# NRF24L01P.net
KiCad netlist of a schematic drawn in Altium Designer
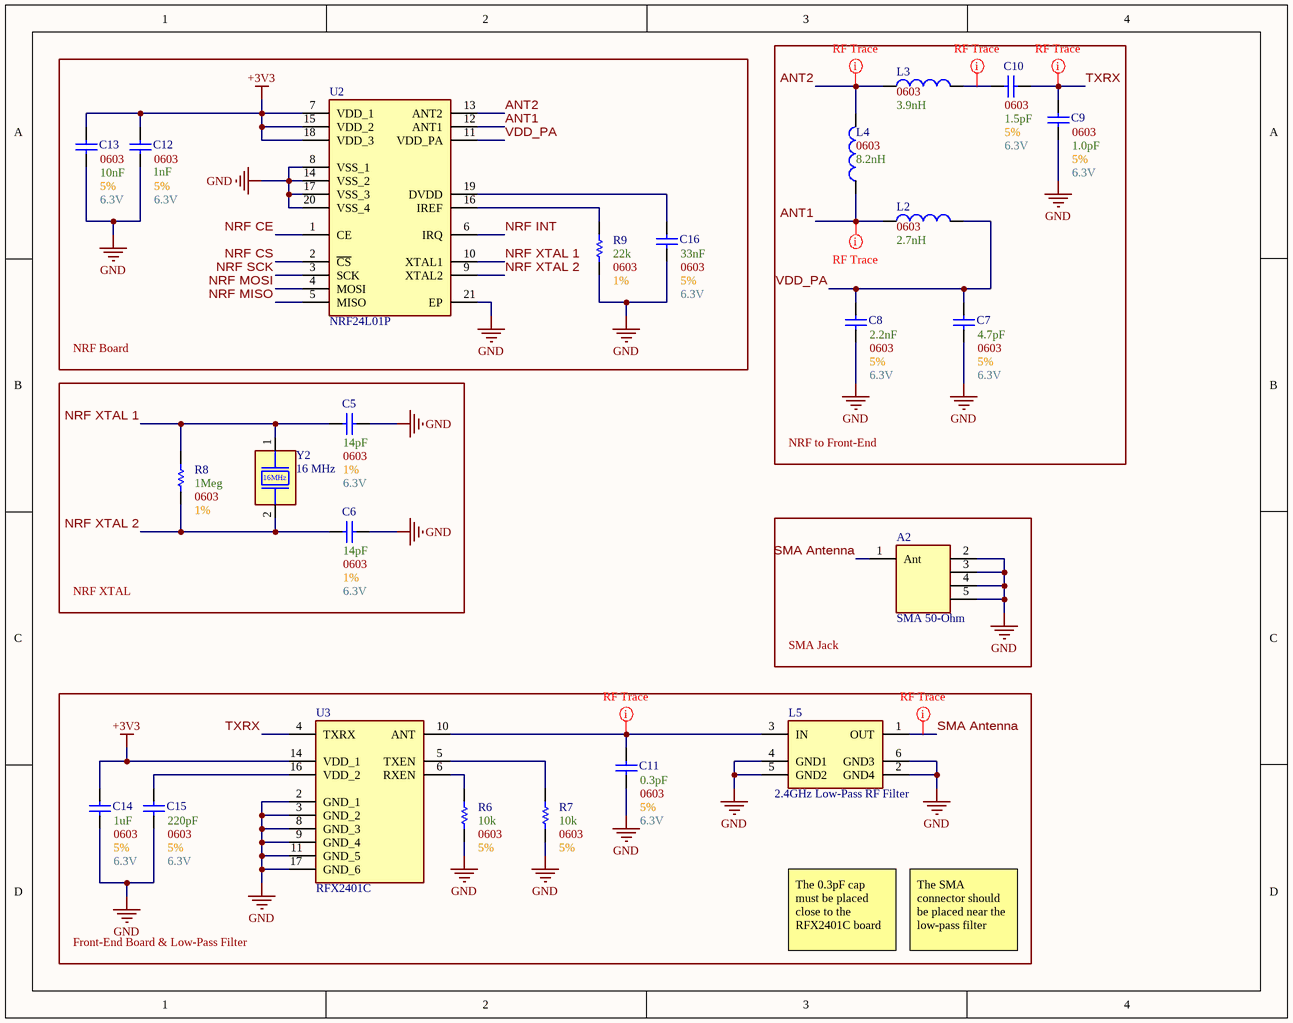
[diagram p0: NRF24L01P.SchDoc]

(export (version "E")
  (design (tool "Eeschema 10.0.6"))
  (components
    (comp (ref "A2")
      (value "SMA 50-Ohm")
      (footprint "[SMA] 90deg Jack")
      (description "SMA-J-P-H-RA-TH1")
      (libsource (lib "RADM Connectors") (part "[SMA] 90deg Jack"))
    )
    (comp (ref "C5")
      (value "SMD Nonpolarized")
      (footprint "[Cap] SMD 0603")
      (fields
        (field (name "TOLERANCE") "1%")
        (field (name "SIZE PACKAGE") "0603")
        (field (name "CAPACITANCE") "14pF")
        (field (name "VOLTAGE") "6.3V")
      )
      (libsource (lib "RADM Components") (part "[Cap] SMD Nonpolarized"))
    )
    (comp (ref "C6")
      (value "SMD Nonpolarized")
      (footprint "[Cap] SMD 0603")
      (fields
        (field (name "TOLERANCE") "1%")
        (field (name "SIZE PACKAGE") "0603")
        (field (name "CAPACITANCE") "14pF")
        (field (name "VOLTAGE") "6.3V")
      )
      (libsource (lib "RADM Components") (part "[Cap] SMD Nonpolarized"))
    )
    (comp (ref "C7")
      (value "SMD Nonpolarized")
      (footprint "[Cap] SMD 0603")
      (fields
        (field (name "TOLERANCE") "5%")
        (field (name "SIZE PACKAGE") "0603")
        (field (name "CAPACITANCE") "4.7pF")
        (field (name "VOLTAGE") "6.3V")
      )
      (libsource (lib "RADM Components") (part "[Cap] SMD Nonpolarized"))
    )
    (comp (ref "C8")
      (value "SMD Nonpolarized")
      (footprint "[Cap] SMD 0603")
      (fields
        (field (name "TOLERANCE") "5%")
        (field (name "SIZE PACKAGE") "0603")
        (field (name "CAPACITANCE") "2.2nF")
        (field (name "VOLTAGE") "6.3V")
      )
      (libsource (lib "RADM Components") (part "[Cap] SMD Nonpolarized"))
    )
    (comp (ref "C9")
      (value "SMD Nonpolarized")
      (footprint "[Cap] SMD 0603")
      (fields
        (field (name "TOLERANCE") "5%")
        (field (name "SIZE PACKAGE") "0603")
        (field (name "CAPACITANCE") "1.0pF")
        (field (name "VOLTAGE") "6.3V")
      )
      (libsource (lib "RADM Components") (part "[Cap] SMD Nonpolarized"))
    )
    (comp (ref "C10")
      (value "SMD Nonpolarized")
      (footprint "[Cap] SMD 0603")
      (fields
        (field (name "TOLERANCE") "5%")
        (field (name "SIZE PACKAGE") "0603")
        (field (name "CAPACITANCE") "1.5pF")
        (field (name "VOLTAGE") "6.3V")
      )
      (libsource (lib "RADM Components") (part "[Cap] SMD Nonpolarized"))
    )
    (comp (ref "C11")
      (value "SMD Nonpolarized")
      (footprint "[Cap] SMD 0603")
      (fields
        (field (name "TOLERANCE") "5%")
        (field (name "SIZE PACKAGE") "0603")
        (field (name "CAPACITANCE") "0.3pF")
        (field (name "VOLTAGE") "6.3V")
      )
      (libsource (lib "RADM Components") (part "[Cap] SMD Nonpolarized"))
    )
    (comp (ref "C12")
      (value "SMD Nonpolarized")
      (footprint "[Cap] SMD 0603")
      (fields
        (field (name "TOLERANCE") "5%")
        (field (name "SIZE PACKAGE") "0603")
        (field (name "CAPACITANCE") "1nF")
        (field (name "VOLTAGE") "6.3V")
      )
      (libsource (lib "RADM Components") (part "[Cap] SMD Nonpolarized"))
    )
    (comp (ref "C13")
      (value "SMD Nonpolarized")
      (footprint "[Cap] SMD 0603")
      (fields
        (field (name "TOLERANCE") "5%")
        (field (name "SIZE PACKAGE") "0603")
        (field (name "CAPACITANCE") "10nF")
        (field (name "VOLTAGE") "6.3V")
      )
      (libsource (lib "RADM Components") (part "[Cap] SMD Nonpolarized"))
    )
    (comp (ref "C14")
      (value "SMD Nonpolarized")
      (footprint "[Cap] SMD 0603")
      (fields
        (field (name "TOLERANCE") "5%")
        (field (name "SIZE PACKAGE") "0603")
        (field (name "CAPACITANCE") "1uF")
        (field (name "VOLTAGE") "6.3V")
      )
      (libsource (lib "RADM Components") (part "[Cap] SMD Nonpolarized"))
    )
    (comp (ref "C15")
      (value "SMD Nonpolarized")
      (footprint "[Cap] SMD 0603")
      (fields
        (field (name "TOLERANCE") "5%")
        (field (name "SIZE PACKAGE") "0603")
        (field (name "CAPACITANCE") "220pF")
        (field (name "VOLTAGE") "6.3V")
      )
      (libsource (lib "RADM Components") (part "[Cap] SMD Nonpolarized"))
    )
    (comp (ref "C16")
      (value "SMD Nonpolarized")
      (footprint "[Cap] SMD 0603")
      (fields
        (field (name "TOLERANCE") "5%")
        (field (name "SIZE PACKAGE") "0603")
        (field (name "CAPACITANCE") "33nF")
        (field (name "VOLTAGE") "6.3V")
      )
      (libsource (lib "RADM Components") (part "[Cap] SMD Nonpolarized"))
    )
    (comp (ref "L2")
      (value "SMD Inductor")
      (footprint "[Inductor] SMD 0603")
      (fields (field (name "SIZE PACKAGE") "0603") (field (name "INDUCTANCE") "2.7nH"))
      (libsource (lib "RADM Components") (part "[Inductor] SMD Inductor"))
    )
    (comp (ref "L3")
      (value "SMD Inductor")
      (footprint "[Inductor] SMD 0603")
      (fields (field (name "SIZE PACKAGE") "0603") (field (name "INDUCTANCE") "3.9nH"))
      (libsource (lib "RADM Components") (part "[Inductor] SMD Inductor"))
    )
    (comp (ref "L4")
      (value "SMD Inductor")
      (footprint "[Inductor] SMD 0603")
      (fields (field (name "SIZE PACKAGE") "0603") (field (name "INDUCTANCE") "8.2nH"))
      (libsource (lib "RADM Components") (part "[Inductor] SMD Inductor"))
    )
    (comp (ref "L5")
      (value "2.4GHz Low-Pass RF Filter")
      (footprint "[Inductor] 2.4GHz Low-Pass RF Filter")
      (description "MLPF-NRG-01D3")
      (libsource (lib "RADM Components") (part "[Inductor] 2.4GHz Low-Pass RF Filter"))
    )
    (comp (ref "R6")
      (value "[Res] SMD Resistor")
      (footprint "[Res] SMD 0603")
      (description "Generic")
      (fields
        (field (name "TOLERANCE") "5%")
        (field (name "RESISTANCE") "10k")
        (field (name "SIZE PACKAGE") "0603")
      )
      (libsource (lib "RADM Components") (part "[Res] SMD Resistor"))
    )
    (comp (ref "R7")
      (value "[Res] SMD Resistor")
      (footprint "[Res] SMD 0603")
      (description "Generic")
      (fields
        (field (name "TOLERANCE") "5%")
        (field (name "RESISTANCE") "10k")
        (field (name "SIZE PACKAGE") "0603")
      )
      (libsource (lib "RADM Components") (part "[Res] SMD Resistor"))
    )
    (comp (ref "R8")
      (value "[Res] SMD Resistor")
      (footprint "[Res] SMD 0603")
      (description "Generic")
      (fields
        (field (name "TOLERANCE") "1%")
        (field (name "RESISTANCE") "1Meg")
        (field (name "SIZE PACKAGE") "0603")
      )
      (libsource (lib "RADM Components") (part "[Res] SMD Resistor"))
    )
    (comp (ref "R9")
      (value "[Res] SMD Resistor")
      (footprint "[Res] SMD 0603")
      (description "Generic")
      (fields
        (field (name "TOLERANCE") "1%")
        (field (name "RESISTANCE") "22k")
        (field (name "SIZE PACKAGE") "0603")
      )
      (libsource (lib "RADM Components") (part "[Res] SMD Resistor"))
    )
    (comp (ref "U2")
      (value "NRF24L01P")
      (footprint "[IC] NRF Transceiver")
      (description "NRF24L01P-R")
      (libsource (lib "RADM Components") (part "[IC] NRF Transceiver"))
    )
    (comp (ref "U3")
      (value "RFX2401C")
      (footprint "[IC] RF Front-End")
      (libsource (lib "RADM Components") (part "[IC] RF Front-End"))
    )
    (comp (ref "Y2")
      (value "16 MHz")
      (footprint "[XTAL] SMD 16MHz (2)")
      (description "ABM11-16.000MHZ-12-N1G-T")
      (libsource (lib "RADM Components") (part "[XTAL] SMD 16MHz (2)"))
    )
  )
  (nets
    (net (code "1") (name "+3V3") (class "Default")
      (node (ref "C12") (pin "2") (pinfunction "2_2") (pintype "passive"))
      (node (ref "C13") (pin "2") (pinfunction "2_2") (pintype "passive"))
      (node (ref "C14") (pin "2") (pinfunction "2_2") (pintype "passive"))
      (node (ref "U2") (pin "15") (pinfunction "VDD_2_15") (pintype "passive"))
      (node (ref "U2") (pin "18") (pinfunction "VDD_3_18") (pintype "passive"))
      (node (ref "U2") (pin "7") (pinfunction "VDD_1_7") (pintype "passive"))
      (node (ref "U3") (pin "14") (pinfunction "VDD_1_14") (pintype "passive"))
    )
    (net (code "2") (name "/ANT1") (class "Default")
      (node (ref "L2") (pin "1") (pinfunction "1_1") (pintype "passive"))
      (node (ref "L4") (pin "1") (pinfunction "1_1") (pintype "passive"))
      (node (ref "U2") (pin "12") (pinfunction "ANT1_12") (pintype "passive"))
    )
    (net (code "3") (name "/ANT2") (class "Default")
      (node (ref "L3") (pin "1") (pinfunction "1_1") (pintype "passive"))
      (node (ref "L4") (pin "2") (pinfunction "2_2") (pintype "passive"))
      (node (ref "U2") (pin "13") (pinfunction "ANT2_13") (pintype "passive"))
    )
    (net (code "4") (name "/NRF CE") (class "Default")
      (node (ref "U2") (pin "1") (pinfunction "CE_1") (pintype "passive"))
    )
    (net (code "5") (name "/NRF CS") (class "Default")
      (node (ref "U2") (pin "2") (pinfunction "CS_2") (pintype "passive"))
    )
    (net (code "6") (name "/NRF INT") (class "Default")
      (node (ref "U2") (pin "6") (pinfunction "IRQ_6") (pintype "passive"))
    )
    (net (code "7") (name "/NRF MISO") (class "Default")
      (node (ref "U2") (pin "5") (pinfunction "MISO_5") (pintype "passive"))
    )
    (net (code "8") (name "/NRF MOSI") (class "Default")
      (node (ref "U2") (pin "4") (pinfunction "MOSI_4") (pintype "passive"))
    )
    (net (code "9") (name "/NRF SCK") (class "Default")
      (node (ref "U2") (pin "3") (pinfunction "SCK_3") (pintype "passive"))
    )
    (net (code "10") (name "/NRF XTAL 1") (class "Default")
      (node (ref "C5") (pin "1") (pinfunction "1_1") (pintype "passive"))
      (node (ref "R8") (pin "2") (pinfunction "2_2") (pintype "passive"))
      (node (ref "U2") (pin "10") (pinfunction "XTAL1_10") (pintype "passive"))
      (node (ref "Y2") (pin "1") (pinfunction "XTAL1_1") (pintype "passive"))
    )
    (net (code "11") (name "/NRF XTAL 2") (class "Default")
      (node (ref "C6") (pin "1") (pinfunction "1_1") (pintype "passive"))
      (node (ref "R8") (pin "1") (pinfunction "1_1") (pintype "passive"))
      (node (ref "U2") (pin "9") (pinfunction "XTAL2_9") (pintype "passive"))
      (node (ref "Y2") (pin "2") (pinfunction "XTAL2_2") (pintype "passive"))
    )
    (net (code "12") (name "/SMA Antenna") (class "Default")
      (node (ref "A2") (pin "1") (pinfunction "Ant_1") (pintype "passive"))
      (node (ref "L5") (pin "1") (pinfunction "OUT_1") (pintype "passive"))
    )
    (net (code "13") (name "/TXRX") (class "Default")
      (node (ref "C10") (pin "1") (pinfunction "1_1") (pintype "passive"))
      (node (ref "C9") (pin "1") (pinfunction "1_1") (pintype "passive"))
      (node (ref "U3") (pin "4") (pinfunction "TXRX_4") (pintype "passive"))
    )
    (net (code "14") (name "/VDD_PA") (class "Default")
      (node (ref "C7") (pin "2") (pinfunction "2_2") (pintype "passive"))
      (node (ref "C8") (pin "2") (pinfunction "2_2") (pintype "passive"))
      (node (ref "L2") (pin "2") (pinfunction "2_2") (pintype "passive"))
      (node (ref "U2") (pin "11") (pinfunction "VDD_PA_11") (pintype "passive"))
    )
    (net (code "15") (name "GND") (class "Default")
      (node (ref "A2") (pin "2") (pinfunction "2_2") (pintype "passive"))
      (node (ref "A2") (pin "3") (pinfunction "3_3") (pintype "passive"))
      (node (ref "A2") (pin "4") (pinfunction "4_4") (pintype "passive"))
      (node (ref "A2") (pin "5") (pinfunction "5_5") (pintype "passive"))
      (node (ref "C11") (pin "1") (pinfunction "1_1") (pintype "passive"))
      (node (ref "C12") (pin "1") (pinfunction "1_1") (pintype "passive"))
      (node (ref "C13") (pin "1") (pinfunction "1_1") (pintype "passive"))
      (node (ref "C14") (pin "1") (pinfunction "1_1") (pintype "passive"))
      (node (ref "C15") (pin "1") (pinfunction "1_1") (pintype "passive"))
      (node (ref "C16") (pin "1") (pinfunction "1_1") (pintype "passive"))
      (node (ref "C5") (pin "2") (pinfunction "2_2") (pintype "passive"))
      (node (ref "C6") (pin "2") (pinfunction "2_2") (pintype "passive"))
      (node (ref "C7") (pin "1") (pinfunction "1_1") (pintype "passive"))
      (node (ref "C8") (pin "1") (pinfunction "1_1") (pintype "passive"))
      (node (ref "C9") (pin "2") (pinfunction "2_2") (pintype "passive"))
      (node (ref "L5") (pin "2") (pinfunction "GND4_2") (pintype "passive"))
      (node (ref "L5") (pin "4") (pinfunction "GND1_4") (pintype "passive"))
      (node (ref "L5") (pin "5") (pinfunction "GND2_5") (pintype "passive"))
      (node (ref "L5") (pin "6") (pinfunction "GND3_6") (pintype "passive"))
      (node (ref "R6") (pin "1") (pinfunction "1_1") (pintype "passive"))
      (node (ref "R7") (pin "1") (pinfunction "1_1") (pintype "passive"))
      (node (ref "R9") (pin "1") (pinfunction "1_1") (pintype "passive"))
      (node (ref "U2") (pin "14") (pinfunction "VSS_2_14") (pintype "passive"))
      (node (ref "U2") (pin "17") (pinfunction "VSS_3_17") (pintype "passive"))
      (node (ref "U2") (pin "20") (pinfunction "VSS_4_20") (pintype "passive"))
      (node (ref "U2") (pin "21") (pinfunction "EP_21") (pintype "passive"))
      (node (ref "U2") (pin "8") (pinfunction "VSS_1_8") (pintype "passive"))
      (node (ref "U3") (pin "11") (pinfunction "GND_5_11") (pintype "passive"))
      (node (ref "U3") (pin "17") (pinfunction "GND_6_17") (pintype "passive"))
      (node (ref "U3") (pin "2") (pinfunction "GND_1_2") (pintype "passive"))
      (node (ref "U3") (pin "3") (pinfunction "GND_2_3") (pintype "passive"))
      (node (ref "U3") (pin "8") (pinfunction "GND_3_8") (pintype "passive"))
      (node (ref "U3") (pin "9") (pinfunction "GND_4_9") (pintype "passive"))
    )
    (net (code "16") (name "Net-(C10-Pad2)") (class "Default")
      (node (ref "C10") (pin "2") (pinfunction "2_2") (pintype "passive"))
      (node (ref "L3") (pin "2") (pinfunction "2_2") (pintype "passive"))
    )
    (net (code "17") (name "Net-(L5-IN)") (class "Default")
      (node (ref "C11") (pin "2") (pinfunction "2_2") (pintype "passive"))
      (node (ref "L5") (pin "3") (pinfunction "IN_3") (pintype "passive"))
      (node (ref "U3") (pin "10") (pinfunction "ANT_10") (pintype "passive"))
    )
    (net (code "18") (name "Net-(U2-DVDD)") (class "Default")
      (node (ref "C16") (pin "2") (pinfunction "2_2") (pintype "passive"))
      (node (ref "U2") (pin "19") (pinfunction "DVDD_19") (pintype "passive"))
    )
    (net (code "19") (name "Net-(U2-IREF)") (class "Default")
      (node (ref "R9") (pin "2") (pinfunction "2_2") (pintype "passive"))
      (node (ref "U2") (pin "16") (pinfunction "IREF_16") (pintype "passive"))
    )
    (net (code "20") (name "Net-(U3-RXEN)") (class "Default")
      (node (ref "R6") (pin "2") (pinfunction "2_2") (pintype "passive"))
      (node (ref "U3") (pin "6") (pinfunction "RXEN_6") (pintype "passive"))
    )
    (net (code "21") (name "Net-(U3-TXEN)") (class "Default")
      (node (ref "R7") (pin "2") (pinfunction "2_2") (pintype "passive"))
      (node (ref "U3") (pin "5") (pinfunction "TXEN_5") (pintype "passive"))
    )
    (net (code "22") (name "Net-(U3-VDD_2)") (class "Default")
      (node (ref "C15") (pin "2") (pinfunction "2_2") (pintype "passive"))
      (node (ref "U3") (pin "16") (pinfunction "VDD_2_16") (pintype "passive"))
    )
  )
)
